# ECE411-Group6-Final.net
KiCad netlist of a schematic drawn in EAGLE
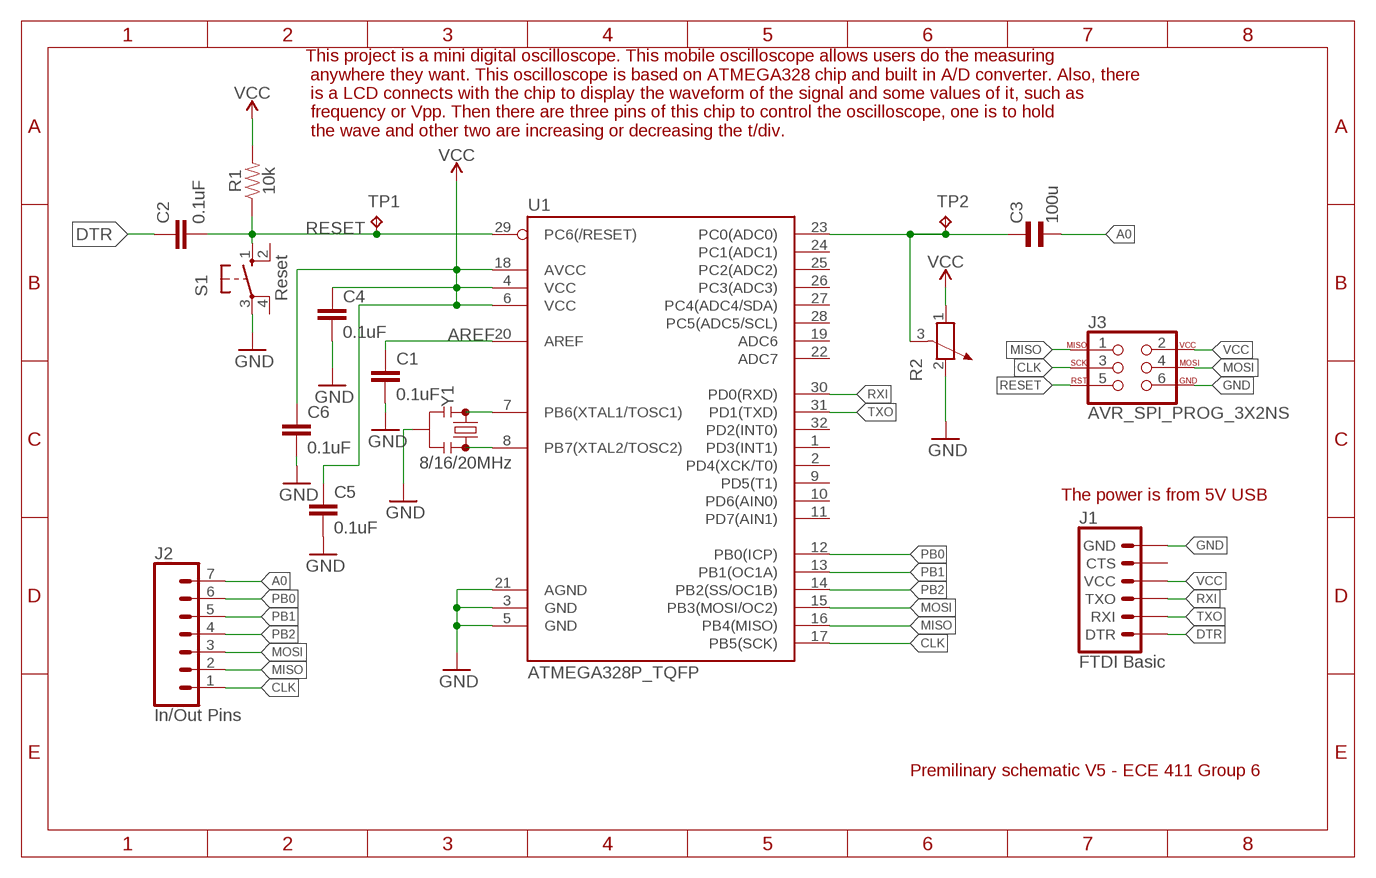
[diagram p0: schematic, sheet 1]

(export (version "E")
  (design (tool "Eeschema 10.0.6"))
  (components
    (comp (ref "C1")
      (value "0.1uF")
      (footprint "eagle-import:0603")
      (libsource (lib "eagle-import") (part "0.1UF-0603-25V-5%"))
    )
    (comp (ref "C2")
      (value "0.1uF")
      (footprint "eagle-import:0603")
      (libsource (lib "eagle-import") (part "0.1UF-0603-25V-5%"))
    )
    (comp (ref "C3")
      (value "100u")
      (footprint "eagle-import:EU25-10")
      (libsource (lib "eagle-import") (part "EL-BI25-10AXIAL"))
    )
    (comp (ref "C4")
      (value "0.1uF")
      (footprint "eagle-import:0603")
      (libsource (lib "eagle-import") (part "0.1UF-0603-25V-5%"))
    )
    (comp (ref "C5")
      (value "0.1uF")
      (footprint "eagle-import:0603")
      (libsource (lib "eagle-import") (part "0.1UF-0603-25V-5%"))
    )
    (comp (ref "C6")
      (value "0.1uF")
      (footprint "eagle-import:0603")
      (libsource (lib "eagle-import") (part "0.1UF-0603-25V-5%"))
    )
    (comp (ref "J1")
      (value "FTDI Basic")
      (footprint "eagle-import:1X06")
      (libsource (lib "eagle-import") (part "6_PIN_SERIAL_TARGET"))
    )
    (comp (ref "J2")
      (value "In/Out Pins")
      (footprint "eagle-import:1X07")
      (libsource (lib "eagle-import") (part "CONN_07"))
    )
    (comp (ref "J3")
      (value "AVR_SPI_PROG_3X2NS")
      (footprint "eagle-import:2X3-NS")
      (libsource (lib "eagle-import") (part "AVR_SPI_PROG_3X2NS"))
    )
    (comp (ref "R1")
      (value "10k")
      (footprint "eagle-import:0603")
      (libsource (lib "eagle-import") (part "10KOHM-0603-1/10W-1%"))
    )
    (comp (ref "R2")
      (value "POTENTIOMETER_PT-10")
      (footprint "eagle-import:PT-10")
      (libsource (lib "eagle-import") (part "POTENTIOMETER_PT-10"))
    )
    (comp (ref "S1")
      (value "Reset")
      (footprint "eagle-import:B3F-10XX")
      (fields (field (name "MPN") "B3F-1000"))
      (libsource (lib "eagle-import") (part "10-XX"))
    )
    (comp (ref "TP1")
      (value "TPB1,27")
      (footprint "eagle-import:B1,27")
      (libsource (lib "eagle-import") (part "TPB1,27"))
    )
    (comp (ref "TP2")
      (value "TPB1,27")
      (footprint "eagle-import:B1,27")
      (libsource (lib "eagle-import") (part "TPB1,27"))
    )
    (comp (ref "U1")
      (value "ATMEGA328P_TQFP")
      (footprint "eagle-import:TQFP32-08")
      (libsource (lib "eagle-import") (part "ATMEGA328P_TQFP"))
    )
    (comp (ref "Y1")
      (value "8/16/20MHz")
      (footprint "eagle-import:RESONATOR-SMD-3.2X1.3")
      (libsource (lib "eagle-import") (part "RESONATORSMD-3.2X1.3"))
    )
  )
  (nets
    (net (code "1") (name "/AREF") (class "Default")
      (node (ref "C1") (pin "1") (pinfunction "1_1") (pintype "passive"))
      (node (ref "U1") (pin "20") (pinfunction "AREF_20") (pintype "bidirectional"))
    )
    (net (code "2") (name "A0") (class "Default")
      (node (ref "C3") (pin "2") (pinfunction "2_2") (pintype "passive"))
      (node (ref "J2") (pin "7") (pinfunction "7_7") (pintype "passive"))
    )
    (net (code "3") (name "CLK") (class "Default")
      (node (ref "J2") (pin "1") (pinfunction "1_1") (pintype "passive"))
      (node (ref "J3") (pin "3") (pinfunction "3_3") (pintype "passive"))
      (node (ref "U1") (pin "17") (pinfunction "PB5(SCK)_17") (pintype "bidirectional"))
    )
    (net (code "4") (name "DTR") (class "Default")
      (node (ref "C2") (pin "1") (pinfunction "1_1") (pintype "passive"))
      (node (ref "J1") (pin "1") (pinfunction "DTR_1") (pintype "passive"))
    )
    (net (code "5") (name "GND") (class "Default")
      (node (ref "C1") (pin "2") (pinfunction "2_2") (pintype "passive"))
      (node (ref "C4") (pin "2") (pinfunction "2_2") (pintype "passive"))
      (node (ref "C5") (pin "2") (pinfunction "2_2") (pintype "passive"))
      (node (ref "C6") (pin "2") (pinfunction "2_2") (pintype "passive"))
      (node (ref "J1") (pin "6") (pinfunction "GND_6") (pintype "passive"))
      (node (ref "J3") (pin "6") (pinfunction "6_6") (pintype "passive"))
      (node (ref "R2") (pin "2") (pinfunction "2_2") (pintype "passive"))
      (node (ref "S1") (pin "3") (pinfunction "P_3") (pintype "passive"))
      (node (ref "U1") (pin "21") (pinfunction "AGND_21") (pintype "bidirectional"))
      (node (ref "U1") (pin "3") (pinfunction "GND_3") (pintype "bidirectional"))
      (node (ref "U1") (pin "5") (pinfunction "GND_5") (pintype "bidirectional"))
      (node (ref "Y1") (pin "2") (pinfunction "2_2") (pintype "passive"))
    )
    (net (code "6") (name "MISO") (class "Default")
      (node (ref "J2") (pin "2") (pinfunction "2_2") (pintype "passive"))
      (node (ref "J3") (pin "1") (pinfunction "1_1") (pintype "passive"))
      (node (ref "U1") (pin "16") (pinfunction "PB4(MISO)_16") (pintype "bidirectional"))
    )
    (net (code "7") (name "MOSI") (class "Default")
      (node (ref "J2") (pin "3") (pinfunction "3_3") (pintype "passive"))
      (node (ref "J3") (pin "4") (pinfunction "4_4") (pintype "passive"))
      (node (ref "U1") (pin "15") (pinfunction "PB3(MOSI/OC2)_15") (pintype "bidirectional"))
    )
    (net (code "8") (name "Net-(U1-PB6(XTAL1{slash}TOSC1))") (class "Default")
      (node (ref "U1") (pin "7") (pinfunction "PB6(XTAL1/TOSC1)_7") (pintype "bidirectional"))
      (node (ref "Y1") (pin "1") (pinfunction "1_1") (pintype "passive"))
    )
    (net (code "9") (name "Net-(U1-PB7(XTAL2{slash}TOSC2))") (class "Default")
      (node (ref "U1") (pin "8") (pinfunction "PB7(XTAL2/TOSC2)_8") (pintype "bidirectional"))
      (node (ref "Y1") (pin "3") (pinfunction "3_3") (pintype "passive"))
    )
    (net (code "10") (name "Net-(U1-PC0(ADC0))") (class "Default")
      (node (ref "C3") (pin "1") (pinfunction "1_1") (pintype "passive"))
      (node (ref "R2") (pin "3") (pinfunction "3_3") (pintype "passive"))
      (node (ref "TP2") (pin "TP") (pinfunction "TP_TP") (pintype "input"))
      (node (ref "U1") (pin "23") (pinfunction "PC0(ADC0)_23") (pintype "bidirectional"))
    )
    (net (code "11") (name "PB0") (class "Default")
      (node (ref "J2") (pin "6") (pinfunction "6_6") (pintype "passive"))
      (node (ref "U1") (pin "12") (pinfunction "PB0(ICP)_12") (pintype "bidirectional"))
    )
    (net (code "12") (name "PB1") (class "Default")
      (node (ref "J2") (pin "5") (pinfunction "5_5") (pintype "passive"))
      (node (ref "U1") (pin "13") (pinfunction "PB1(OC1A)_13") (pintype "bidirectional"))
    )
    (net (code "13") (name "PB2") (class "Default")
      (node (ref "J2") (pin "4") (pinfunction "4_4") (pintype "passive"))
      (node (ref "U1") (pin "14") (pinfunction "PB2(SS/OC1B)_14") (pintype "bidirectional"))
    )
    (net (code "14") (name "RESET") (class "Default")
      (node (ref "C2") (pin "2") (pinfunction "2_2") (pintype "passive"))
      (node (ref "J3") (pin "5") (pinfunction "5_5") (pintype "passive"))
      (node (ref "R1") (pin "1") (pinfunction "1_1") (pintype "passive"))
      (node (ref "S1") (pin "1") (pinfunction "S_1") (pintype "passive"))
      (node (ref "TP1") (pin "TP") (pinfunction "TP_TP") (pintype "input"))
      (node (ref "U1") (pin "29") (pinfunction "PC6(/RESET)_29") (pintype "bidirectional"))
    )
    (net (code "15") (name "RXI") (class "Default")
      (node (ref "J1") (pin "3") (pinfunction "TXO_3") (pintype "passive"))
      (node (ref "U1") (pin "30") (pinfunction "PD0(RXD)_30") (pintype "bidirectional"))
    )
    (net (code "16") (name "TXO") (class "Default")
      (node (ref "J1") (pin "2") (pinfunction "RXI_2") (pintype "passive"))
      (node (ref "U1") (pin "31") (pinfunction "PD1(TXD)_31") (pintype "bidirectional"))
    )
    (net (code "17") (name "VCC") (class "Default")
      (node (ref "C4") (pin "1") (pinfunction "1_1") (pintype "passive"))
      (node (ref "C5") (pin "1") (pinfunction "1_1") (pintype "passive"))
      (node (ref "C6") (pin "1") (pinfunction "1_1") (pintype "passive"))
      (node (ref "J1") (pin "4") (pinfunction "VCC_4") (pintype "passive"))
      (node (ref "J3") (pin "2") (pinfunction "2_2") (pintype "passive"))
      (node (ref "R1") (pin "2") (pinfunction "2_2") (pintype "passive"))
      (node (ref "R2") (pin "1") (pinfunction "1_1") (pintype "passive"))
      (node (ref "U1") (pin "18") (pinfunction "AVCC_18") (pintype "bidirectional"))
      (node (ref "U1") (pin "4") (pinfunction "VCC_4") (pintype "bidirectional"))
      (node (ref "U1") (pin "6") (pinfunction "VCC_6") (pintype "bidirectional"))
    )
    (net (code "18") (name "unconnected-(J1-CTS-Pad5)") (class "Default")
      (node (ref "J1") (pin "5") (pinfunction "CTS_5") (pintype "passive"))
    )
    (net (code "19") (name "unconnected-(S1-P1-Pad4)") (class "Default")
      (node (ref "S1") (pin "4") (pinfunction "P1_4") (pintype "passive"))
    )
    (net (code "20") (name "unconnected-(S1-S1-Pad2)") (class "Default")
      (node (ref "S1") (pin "2") (pinfunction "S1_2") (pintype "passive"))
    )
    (net (code "21") (name "unconnected-(U1-ADC6-Pad19)") (class "Default")
      (node (ref "U1") (pin "19") (pinfunction "ADC6_19") (pintype "bidirectional"))
    )
    (net (code "22") (name "unconnected-(U1-ADC7-Pad22)") (class "Default")
      (node (ref "U1") (pin "22") (pinfunction "ADC7_22") (pintype "bidirectional"))
    )
    (net (code "23") (name "unconnected-(U1-PC1(ADC1)-Pad24)") (class "Default")
      (node (ref "U1") (pin "24") (pinfunction "PC1(ADC1)_24") (pintype "bidirectional"))
    )
    (net (code "24") (name "unconnected-(U1-PC2(ADC2)-Pad25)") (class "Default")
      (node (ref "U1") (pin "25") (pinfunction "PC2(ADC2)_25") (pintype "bidirectional"))
    )
    (net (code "25") (name "unconnected-(U1-PC3(ADC3)-Pad26)") (class "Default")
      (node (ref "U1") (pin "26") (pinfunction "PC3(ADC3)_26") (pintype "bidirectional"))
    )
    (net (code "26") (name "unconnected-(U1-PC4(ADC4{slash}SDA)-Pad27)") (class "Default")
      (node (ref "U1") (pin "27") (pinfunction "PC4(ADC4/SDA)_27") (pintype "bidirectional"))
    )
    (net (code "27") (name "unconnected-(U1-PC5(ADC5{slash}SCL)-Pad28)") (class "Default")
      (node (ref "U1") (pin "28") (pinfunction "PC5(ADC5/SCL)_28") (pintype "bidirectional"))
    )
    (net (code "28") (name "unconnected-(U1-PD2(INT0)-Pad32)") (class "Default")
      (node (ref "U1") (pin "32") (pinfunction "PD2(INT0)_32") (pintype "bidirectional"))
    )
    (net (code "29") (name "unconnected-(U1-PD3(INT1)-Pad1)") (class "Default")
      (node (ref "U1") (pin "1") (pinfunction "PD3(INT1)_1") (pintype "bidirectional"))
    )
    (net (code "30") (name "unconnected-(U1-PD4(XCK{slash}T0)-Pad2)") (class "Default")
      (node (ref "U1") (pin "2") (pinfunction "PD4(XCK/T0)_2") (pintype "bidirectional"))
    )
    (net (code "31") (name "unconnected-(U1-PD5(T1)-Pad9)") (class "Default")
      (node (ref "U1") (pin "9") (pinfunction "PD5(T1)_9") (pintype "bidirectional"))
    )
    (net (code "32") (name "unconnected-(U1-PD6(AIN0)-Pad10)") (class "Default")
      (node (ref "U1") (pin "10") (pinfunction "PD6(AIN0)_10") (pintype "bidirectional"))
    )
    (net (code "33") (name "unconnected-(U1-PD7(AIN1)-Pad11)") (class "Default")
      (node (ref "U1") (pin "11") (pinfunction "PD7(AIN1)_11") (pintype "bidirectional"))
    )
  )
)
